# POWER_RAIL.net
KiCad netlist of a schematic drawn in Altium Designer
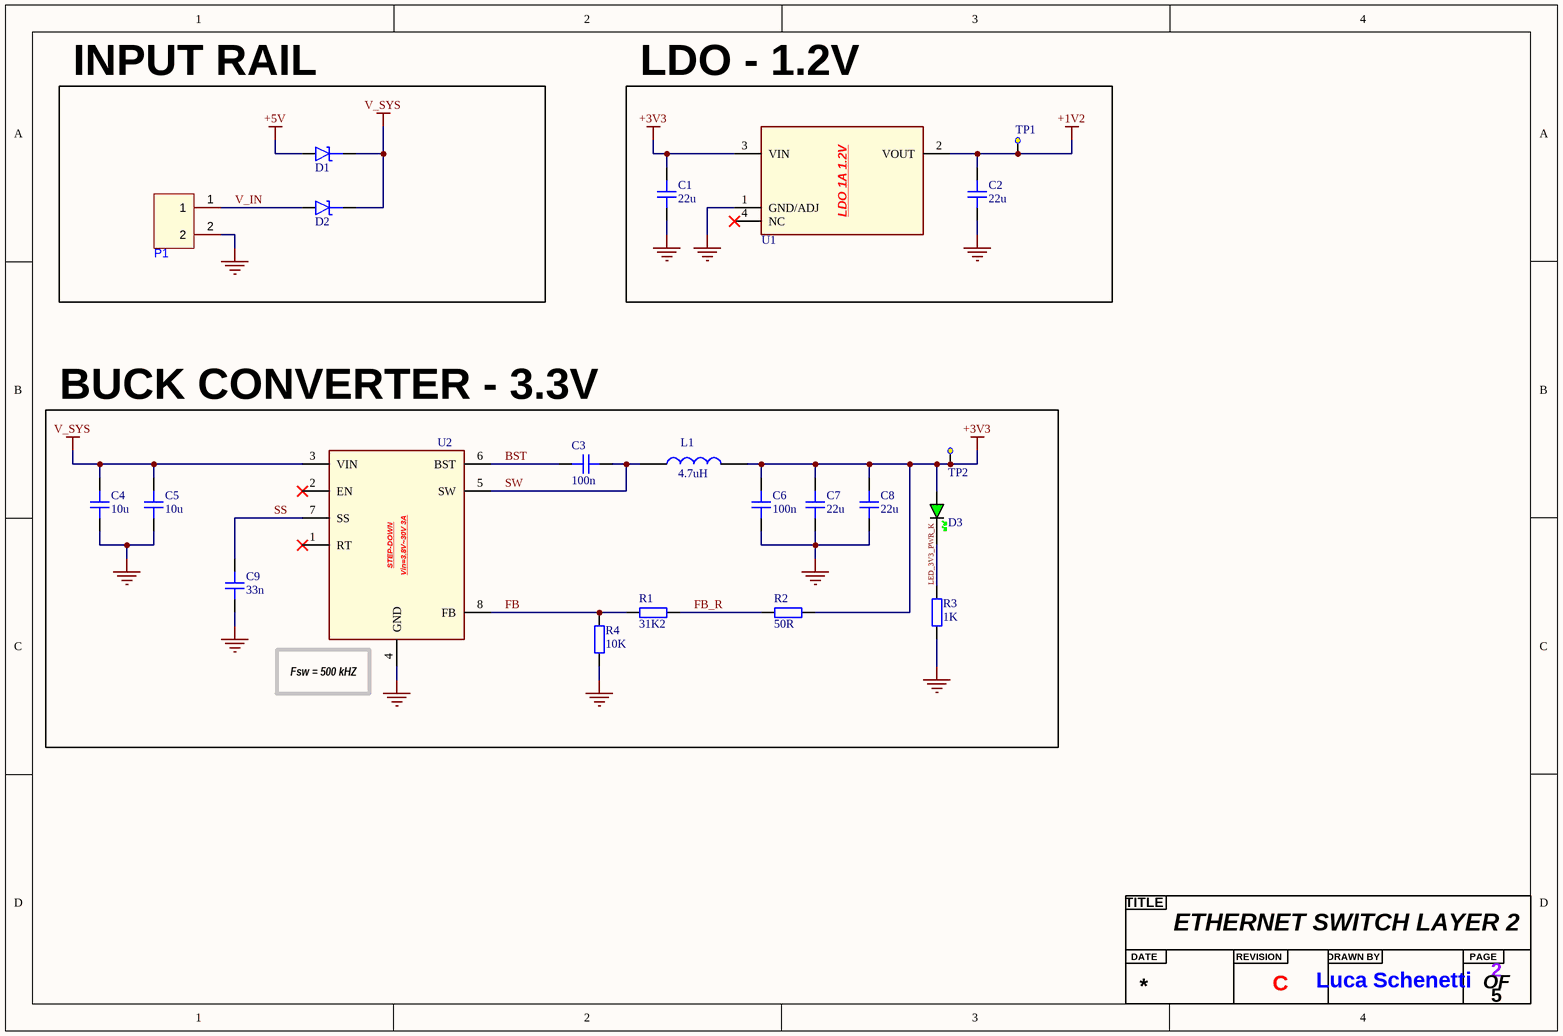
[diagram p0: POWER RAIL.SchDoc]

(export (version "E")
  (design (tool "Eeschema 10.0.6"))
  (components
    (comp (ref "C1")
      (value "22u")
      (footprint "CAP_1206")
      (description "[C12891]")
      (libsource (lib "Schematic-Lib-PhilsLab") (part "CAP_1206"))
    )
    (comp (ref "C2")
      (value "22u")
      (footprint "CAP_1206")
      (description "[C12891]")
      (libsource (lib "Schematic-Lib-PhilsLab") (part "CAP_1206"))
    )
    (comp (ref "C3")
      (value "100n")
      (footprint "CAP_0603")
      (description "Capacitor SMD 0603 [C14663]")
      (libsource (lib "Schematic-Lib-PhilsLab") (part "CAP_0603"))
    )
    (comp (ref "C4")
      (value "10u")
      (footprint "CAP_0805")
      (description "Capacitor SMD 0805[C440198]")
      (libsource (lib "Schematic-Lib-PhilsLab") (part "CAP_0805"))
    )
    (comp (ref "C5")
      (value "10u")
      (footprint "CAP_0805")
      (description "Capacitor SMD 0805[C440198]")
      (libsource (lib "Schematic-Lib-PhilsLab") (part "CAP_0805"))
    )
    (comp (ref "C6")
      (value "100n")
      (footprint "CAP_0603")
      (description "Capacitor SMD 0603 [C14663]")
      (libsource (lib "Schematic-Lib-PhilsLab") (part "CAP_0603"))
    )
    (comp (ref "C7")
      (value "22u")
      (footprint "CAP_0603")
      (description "Capacitor SMD 0603 [C59461]")
      (libsource (lib "Schematic-Lib-PhilsLab") (part "CAP_0603"))
    )
    (comp (ref "C8")
      (value "22u")
      (footprint "CAP_0603")
      (description "Capacitor SMD 0603 [C59461]")
      (libsource (lib "Schematic-Lib-PhilsLab") (part "CAP_0603"))
    )
    (comp (ref "C9")
      (value "33n")
      (footprint "CAP_0603")
      (description "[C21117]")
      (libsource (lib "Schematic-Lib-PhilsLab") (part "CAP_0603"))
    )
    (comp (ref "D1")
      (value "40V 3A SMA(DO-214AC)")
      (footprint "SS34")
      (description "[C8678]")
      (libsource (lib "My_Library") (part "SS34"))
    )
    (comp (ref "D2")
      (value "40V 3A SMA(DO-214AC)")
      (footprint "SS34")
      (description "[C8678]")
      (libsource (lib "My_Library") (part "SS34"))
    )
    (comp (ref "D3")
      (value "GREEN")
      (footprint "LED_0603_GREEN")
      (description "LED 0603 GREEN SMD[C2986059]")
      (libsource (lib "Schematic-Lib-PhilsLab") (part "LED_0603_GREEN"))
    )
    (comp (ref "L1")
      (value "4.7uH")
      (footprint "FXL0530-4R7-M")
      (description "[C177246]")
      (libsource (lib "My_Library") (part "FXL0530-4R7-M"))
    )
    (comp (ref "P1")
      (value "WJ500V-5.08-2P")
      (footprint "CONN-TH_2P-P5.00_WJ500V-5.08-2P")
      (description "[C8465]")
      (fields (field (name "MANUFACTURER") "KANGNEX(康奈克斯电气)"))
      (libsource (lib "My_Library") (part "WJ500V-5.08-2P"))
    )
    (comp (ref "R1")
      (value "31K2")
      (footprint "RES_0603")
      (description "[C863036]")
      (libsource (lib "Schematic-Lib-PhilsLab") (part "RES_0603"))
    )
    (comp (ref "R2")
      (value "50R")
      (footprint "RES_0603")
      (description "[C849792]")
      (libsource (lib "Schematic-Lib-PhilsLab") (part "RES_0603"))
    )
    (comp (ref "R3")
      (value "1K")
      (footprint "RES_0402")
      (description "Resistor SMD 0402 [C11702]")
      (libsource (lib "Schematic-Lib-PhilsLab") (part "RES_0402"))
    )
    (comp (ref "R4")
      (value "10K")
      (footprint "RES_0603")
      (description "[C25804]")
      (libsource (lib "Schematic-Lib-PhilsLab") (part "RES_0603"))
    )
    (comp (ref "TP1")
      (value "Test Point")
      (footprint "Test Point")
      (libsource (lib "SchedaLed") (part "Test Point"))
    )
    (comp (ref "TP2")
      (value "Test Point")
      (footprint "Test Point")
      (libsource (lib "My_Library") (part "Test Point"))
    )
    (comp (ref "U1")
      (value "LDO 1A 1.2V")
      (footprint "AMS1117-1.2")
      (description "[C347218]")
      (libsource (lib "My_Library") (part "AMS1117-1.2"))
    )
    (comp (ref "U2")
      (value "Step Down Converter 3A 3.8V~30V")
      (footprint "TPS62933DRLR")
      (description "[C3200405]")
      (libsource (lib "My_Library") (part "TPS62933DRLR"))
    )
  )
  (nets
    (net (code "1") (name "+1V2") (class "Default")
      (node (ref "C2") (pin "2") (pinfunction "2_2") (pintype "passive"))
      (node (ref "TP1") (pin "1") (pinfunction "Test_Point_1") (pintype "passive"))
      (node (ref "U1") (pin "2") (pinfunction "VOUT_2") (pintype "passive"))
    )
    (net (code "2") (name "+3V3") (class "Default")
      (node (ref "C1") (pin "2") (pinfunction "2_2") (pintype "passive"))
      (node (ref "C6") (pin "1") (pinfunction "1_1") (pintype "passive"))
      (node (ref "C7") (pin "2") (pinfunction "2_2") (pintype "passive"))
      (node (ref "C8") (pin "2") (pinfunction "2_2") (pintype "passive"))
      (node (ref "D3") (pin "A") (pinfunction "A_A") (pintype "passive"))
      (node (ref "L1") (pin "2") (pinfunction "2_2") (pintype "passive"))
      (node (ref "R2") (pin "1") (pinfunction "1_1") (pintype "passive"))
      (node (ref "TP2") (pin "1") (pinfunction "Test_Point_1") (pintype "passive"))
      (node (ref "U1") (pin "3") (pinfunction "VIN_3") (pintype "power_in"))
    )
    (net (code "3") (name "+5V") (class "Default")
      (node (ref "D1") (pin "A") (pinfunction "A_A") (pintype "passive"))
    )
    (net (code "4") (name "/BST") (class "Default")
      (node (ref "C3") (pin "2") (pinfunction "2_2") (pintype "passive"))
      (node (ref "U2") (pin "6") (pinfunction "BST_6") (pintype "passive"))
    )
    (net (code "5") (name "/FB") (class "Default")
      (node (ref "R1") (pin "2") (pinfunction "2_2") (pintype "passive"))
      (node (ref "R4") (pin "2") (pinfunction "2_2") (pintype "passive"))
      (node (ref "U2") (pin "8") (pinfunction "FB_8") (pintype "passive"))
    )
    (net (code "6") (name "/FB_R") (class "Default")
      (node (ref "R1") (pin "1") (pinfunction "1_1") (pintype "passive"))
      (node (ref "R2") (pin "2") (pinfunction "2_2") (pintype "passive"))
    )
    (net (code "7") (name "/LED_3V3_PWR_K") (class "Default")
      (node (ref "D3") (pin "K") (pinfunction "K_K") (pintype "passive"))
      (node (ref "R3") (pin "2") (pinfunction "2_2") (pintype "passive"))
    )
    (net (code "8") (name "/SS") (class "Default")
      (node (ref "C9") (pin "1") (pinfunction "1_1") (pintype "passive"))
      (node (ref "U2") (pin "7") (pinfunction "SS_7") (pintype "passive"))
    )
    (net (code "9") (name "/SW") (class "Default")
      (node (ref "C3") (pin "1") (pinfunction "1_1") (pintype "passive"))
      (node (ref "L1") (pin "1") (pinfunction "1_1") (pintype "passive"))
      (node (ref "U2") (pin "5") (pinfunction "SW_5") (pintype "passive"))
    )
    (net (code "10") (name "/V_IN") (class "Default")
      (node (ref "D2") (pin "A") (pinfunction "A_A") (pintype "passive"))
      (node (ref "P1") (pin "1") (pinfunction "1_1") (pintype "passive"))
    )
    (net (code "11") (name "GND") (class "Default")
      (node (ref "C1") (pin "1") (pinfunction "1_1") (pintype "passive"))
      (node (ref "C2") (pin "1") (pinfunction "1_1") (pintype "passive"))
      (node (ref "C4") (pin "1") (pinfunction "1_1") (pintype "passive"))
      (node (ref "C5") (pin "1") (pinfunction "1_1") (pintype "passive"))
      (node (ref "C6") (pin "2") (pinfunction "2_2") (pintype "passive"))
      (node (ref "C7") (pin "1") (pinfunction "1_1") (pintype "passive"))
      (node (ref "C8") (pin "1") (pinfunction "1_1") (pintype "passive"))
      (node (ref "C9") (pin "2") (pinfunction "2_2") (pintype "passive"))
      (node (ref "P1") (pin "2") (pinfunction "2_2") (pintype "passive"))
      (node (ref "R3") (pin "1") (pinfunction "1_1") (pintype "passive"))
      (node (ref "R4") (pin "1") (pinfunction "1_1") (pintype "passive"))
      (node (ref "U1") (pin "1") (pinfunction "GND/ADJ_1") (pintype "passive"))
      (node (ref "U2") (pin "4") (pinfunction "GND_4") (pintype "power_in"))
    )
    (net (code "12") (name "V_SYS") (class "Default")
      (node (ref "C4") (pin "2") (pinfunction "2_2") (pintype "passive"))
      (node (ref "C5") (pin "2") (pinfunction "2_2") (pintype "passive"))
      (node (ref "D1") (pin "K") (pinfunction "K_K") (pintype "passive"))
      (node (ref "D2") (pin "K") (pinfunction "K_K") (pintype "passive"))
      (node (ref "U2") (pin "3") (pinfunction "VIN_3") (pintype "passive"))
    )
    (net (code "13") (name "unconnected-(U1-NC-Pad4)") (class "Default")
      (node (ref "U1") (pin "4") (pinfunction "NC_4") (pintype "passive+no_connect"))
    )
    (net (code "14") (name "unconnected-(U2-EN-Pad2)") (class "Default")
      (node (ref "U2") (pin "2") (pinfunction "EN_2") (pintype "passive+no_connect"))
    )
    (net (code "15") (name "unconnected-(U2-RT-Pad1)") (class "Default")
      (node (ref "U2") (pin "1") (pinfunction "RT_1") (pintype "passive+no_connect"))
    )
  )
)
